# circuit.net
KiCad netlist of a schematic drawn in EAGLE
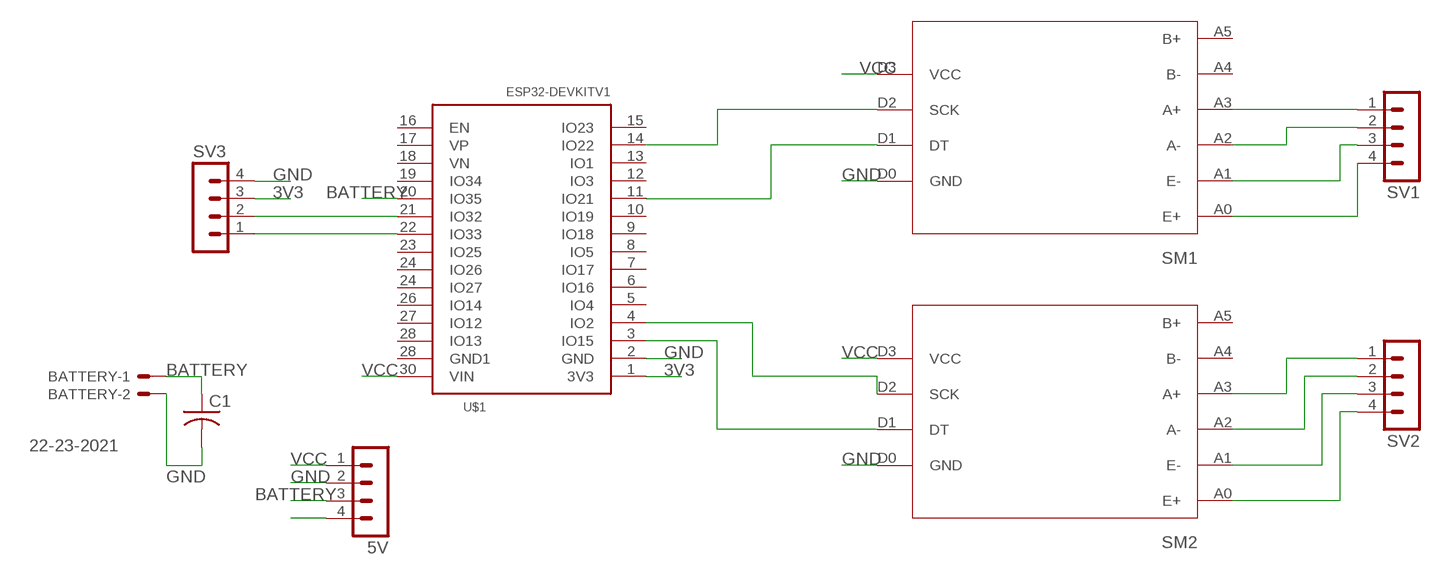
[diagram p0: schematic, sheet 1]

(export (version "E")
  (design (tool "Eeschema 10.0.6"))
  (components
    (comp (ref "5V")
      (value "MA04-1")
      (footprint "eagle-import:MA04-1")
      (libsource (lib "eagle-import") (part "MA04-1"))
    )
    (comp (ref "BATTERY")
      (value "22-23-2021")
      (footprint "eagle-import:22-23-2021")
      (fields (field (name "MF") "MOLEX"))
      (libsource (lib "eagle-import") (part "22-23-2021"))
    )
    (comp (ref "C1")
      (value "C-US050-055X075")
      (footprint "eagle-import:C050-055X075")
      (libsource (lib "eagle-import") (part "C-US050-055X075"))
    )
    (comp (ref "SM1")
      (value "HX711")
      (footprint "eagle-import:HX711")
      (libsource (lib "eagle-import") (part "HX711"))
    )
    (comp (ref "SM2")
      (value "HX711")
      (footprint "eagle-import:HX711")
      (libsource (lib "eagle-import") (part "HX711"))
    )
    (comp (ref "SV1")
      (value "MA04-1")
      (footprint "eagle-import:MA04-1")
      (libsource (lib "eagle-import") (part "MA04-1"))
    )
    (comp (ref "SV2")
      (value "MA04-1")
      (footprint "eagle-import:MA04-1")
      (libsource (lib "eagle-import") (part "MA04-1"))
    )
    (comp (ref "SV3")
      (value "MA04-1")
      (footprint "eagle-import:MA04-1")
      (libsource (lib "eagle-import") (part "MA04-1"))
    )
    (comp (ref "U$1")
      (value "ESP32DEVKITV1")
      (footprint "eagle-import:ESP32-DEVKITV1")
      (libsource (lib "eagle-import") (part "ESP32DEVKITV1"))
    )
  )
  (nets
    (net (code "1") (name "/3V3") (class "Default")
      (node (ref "SV3") (pin "3") (pinfunction "3_3") (pintype "passive"))
      (node (ref "U$1") (pin "1") (pinfunction "3V3_1") (pintype "bidirectional"))
    )
    (net (code "2") (name "/BATTERY") (class "Default")
      (node (ref "5V") (pin "3") (pinfunction "3_3") (pintype "passive"))
      (node (ref "BATTERY") (pin "1") (pinfunction "S_1") (pintype "passive"))
      (node (ref "C1") (pin "1") (pinfunction "1_1") (pintype "passive"))
      (node (ref "U$1") (pin "20") (pinfunction "IO35_20") (pintype "bidirectional"))
    )
    (net (code "3") (name "/GND") (class "Default")
      (node (ref "5V") (pin "2") (pinfunction "2_2") (pintype "passive"))
      (node (ref "BATTERY") (pin "2") (pinfunction "S_2") (pintype "passive"))
      (node (ref "C1") (pin "2") (pinfunction "2_2") (pintype "passive"))
      (node (ref "SM1") (pin "D0") (pinfunction "GND_D0") (pintype "bidirectional"))
      (node (ref "SM2") (pin "D0") (pinfunction "GND_D0") (pintype "bidirectional"))
      (node (ref "SV3") (pin "4") (pinfunction "4_4") (pintype "passive"))
      (node (ref "U$1") (pin "2") (pinfunction "GND_2") (pintype "bidirectional"))
    )
    (net (code "4") (name "/VCC") (class "Default")
      (node (ref "5V") (pin "1") (pinfunction "1_1") (pintype "passive"))
      (node (ref "SM1") (pin "D3") (pinfunction "VCC_D3") (pintype "bidirectional"))
      (node (ref "SM2") (pin "D3") (pinfunction "VCC_D3") (pintype "bidirectional"))
      (node (ref "U$1") (pin "30") (pinfunction "VIN_30") (pintype "bidirectional"))
    )
    (net (code "5") (name "Net-(SM1-A+)") (class "Default")
      (node (ref "SM1") (pin "A3") (pinfunction "A+_A3") (pintype "bidirectional"))
      (node (ref "SV1") (pin "1") (pinfunction "1_1") (pintype "passive"))
    )
    (net (code "6") (name "Net-(SM1-A-)") (class "Default")
      (node (ref "SM1") (pin "A2") (pinfunction "A-_A2") (pintype "bidirectional"))
      (node (ref "SV1") (pin "2") (pinfunction "2_2") (pintype "passive"))
    )
    (net (code "7") (name "Net-(SM1-DT)") (class "Default")
      (node (ref "SM1") (pin "D1") (pinfunction "DT_D1") (pintype "bidirectional"))
      (node (ref "U$1") (pin "11") (pinfunction "IO21_11") (pintype "bidirectional"))
    )
    (net (code "8") (name "Net-(SM1-E+)") (class "Default")
      (node (ref "SM1") (pin "A0") (pinfunction "E+_A0") (pintype "bidirectional"))
      (node (ref "SV1") (pin "4") (pinfunction "4_4") (pintype "passive"))
    )
    (net (code "9") (name "Net-(SM1-E-)") (class "Default")
      (node (ref "SM1") (pin "A1") (pinfunction "E-_A1") (pintype "bidirectional"))
      (node (ref "SV1") (pin "3") (pinfunction "3_3") (pintype "passive"))
    )
    (net (code "10") (name "Net-(SM1-SCK)") (class "Default")
      (node (ref "SM1") (pin "D2") (pinfunction "SCK_D2") (pintype "bidirectional"))
      (node (ref "U$1") (pin "14") (pinfunction "IO22_14") (pintype "bidirectional"))
    )
    (net (code "11") (name "Net-(SM2-A+)") (class "Default")
      (node (ref "SM2") (pin "A3") (pinfunction "A+_A3") (pintype "bidirectional"))
      (node (ref "SV2") (pin "1") (pinfunction "1_1") (pintype "passive"))
    )
    (net (code "12") (name "Net-(SM2-A-)") (class "Default")
      (node (ref "SM2") (pin "A2") (pinfunction "A-_A2") (pintype "bidirectional"))
      (node (ref "SV2") (pin "2") (pinfunction "2_2") (pintype "passive"))
    )
    (net (code "13") (name "Net-(SM2-DT)") (class "Default")
      (node (ref "SM2") (pin "D1") (pinfunction "DT_D1") (pintype "bidirectional"))
      (node (ref "U$1") (pin "3") (pinfunction "IO15_3") (pintype "bidirectional"))
    )
    (net (code "14") (name "Net-(SM2-E+)") (class "Default")
      (node (ref "SM2") (pin "A0") (pinfunction "E+_A0") (pintype "bidirectional"))
      (node (ref "SV2") (pin "4") (pinfunction "4_4") (pintype "passive"))
    )
    (net (code "15") (name "Net-(SM2-E-)") (class "Default")
      (node (ref "SM2") (pin "A1") (pinfunction "E-_A1") (pintype "bidirectional"))
      (node (ref "SV2") (pin "3") (pinfunction "3_3") (pintype "passive"))
    )
    (net (code "16") (name "Net-(SM2-SCK)") (class "Default")
      (node (ref "SM2") (pin "D2") (pinfunction "SCK_D2") (pintype "bidirectional"))
      (node (ref "U$1") (pin "4") (pinfunction "IO2_4") (pintype "bidirectional"))
    )
    (net (code "17") (name "Net-(U$1-IO32)") (class "Default")
      (node (ref "SV3") (pin "2") (pinfunction "2_2") (pintype "passive"))
      (node (ref "U$1") (pin "21") (pinfunction "IO32_21") (pintype "bidirectional"))
    )
    (net (code "18") (name "Net-(U$1-IO33)") (class "Default")
      (node (ref "SV3") (pin "1") (pinfunction "1_1") (pintype "passive"))
      (node (ref "U$1") (pin "22") (pinfunction "IO33_22") (pintype "bidirectional"))
    )
    (net (code "19") (name "unconnected-(5V-Pad4)") (class "Default")
      (node (ref "5V") (pin "4") (pinfunction "4_4") (pintype "passive"))
    )
    (net (code "20") (name "unconnected-(SM1-B+-PadA5)") (class "Default")
      (node (ref "SM1") (pin "A5") (pinfunction "B+_A5") (pintype "bidirectional"))
    )
    (net (code "21") (name "unconnected-(SM1-B--PadA4)") (class "Default")
      (node (ref "SM1") (pin "A4") (pinfunction "B-_A4") (pintype "bidirectional"))
    )
    (net (code "22") (name "unconnected-(SM2-B+-PadA5)") (class "Default")
      (node (ref "SM2") (pin "A5") (pinfunction "B+_A5") (pintype "bidirectional"))
    )
    (net (code "23") (name "unconnected-(SM2-B--PadA4)") (class "Default")
      (node (ref "SM2") (pin "A4") (pinfunction "B-_A4") (pintype "bidirectional"))
    )
    (net (code "24") (name "unconnected-(U$1-EN-Pad16)") (class "Default")
      (node (ref "U$1") (pin "16") (pinfunction "EN_16") (pintype "bidirectional"))
    )
    (net (code "25") (name "unconnected-(U$1-GND1-Pad28)") (class "Default")
      (node (ref "U$1") (pin "28") (pinfunction "GND1_28") (pintype "bidirectional"))
    )
    (net (code "26") (name "unconnected-(U$1-IO1-Pad13)") (class "Default")
      (node (ref "U$1") (pin "13") (pinfunction "IO1_13") (pintype "bidirectional"))
    )
    (net (code "27") (name "unconnected-(U$1-IO3-Pad12)") (class "Default")
      (node (ref "U$1") (pin "12") (pinfunction "IO3_12") (pintype "bidirectional"))
    )
    (net (code "28") (name "unconnected-(U$1-IO4-Pad5)") (class "Default")
      (node (ref "U$1") (pin "5") (pinfunction "IO4_5") (pintype "bidirectional"))
    )
    (net (code "29") (name "unconnected-(U$1-IO5-Pad8)") (class "Default")
      (node (ref "U$1") (pin "8") (pinfunction "IO5_8") (pintype "bidirectional"))
    )
    (net (code "30") (name "unconnected-(U$1-IO12-Pad27)") (class "Default")
      (node (ref "U$1") (pin "27") (pinfunction "IO12_27") (pintype "bidirectional"))
    )
    (net (code "31") (name "unconnected-(U$1-IO13-Pad28)") (class "Default")
      (node (ref "U$1") (pin "28") (pinfunction "IO13_28") (pintype "bidirectional"))
    )
    (net (code "32") (name "unconnected-(U$1-IO14-Pad26)") (class "Default")
      (node (ref "U$1") (pin "26") (pinfunction "IO14_26") (pintype "bidirectional"))
    )
    (net (code "33") (name "unconnected-(U$1-IO16-Pad6)") (class "Default")
      (node (ref "U$1") (pin "6") (pinfunction "IO16_6") (pintype "bidirectional"))
    )
    (net (code "34") (name "unconnected-(U$1-IO17-Pad7)") (class "Default")
      (node (ref "U$1") (pin "7") (pinfunction "IO17_7") (pintype "bidirectional"))
    )
    (net (code "35") (name "unconnected-(U$1-IO18-Pad9)") (class "Default")
      (node (ref "U$1") (pin "9") (pinfunction "IO18_9") (pintype "bidirectional"))
    )
    (net (code "36") (name "unconnected-(U$1-IO19-Pad10)") (class "Default")
      (node (ref "U$1") (pin "10") (pinfunction "IO19_10") (pintype "bidirectional"))
    )
    (net (code "37") (name "unconnected-(U$1-IO23-Pad15)") (class "Default")
      (node (ref "U$1") (pin "15") (pinfunction "IO23_15") (pintype "bidirectional"))
    )
    (net (code "38") (name "unconnected-(U$1-IO25-Pad23)") (class "Default")
      (node (ref "U$1") (pin "23") (pinfunction "IO25_23") (pintype "bidirectional"))
    )
    (net (code "39") (name "unconnected-(U$1-IO26-Pad24)") (class "Default")
      (node (ref "U$1") (pin "24") (pinfunction "IO26_24") (pintype "bidirectional"))
    )
    (net (code "40") (name "unconnected-(U$1-IO27-Pad24)") (class "Default")
      (node (ref "U$1") (pin "24") (pinfunction "IO27_24") (pintype "bidirectional"))
    )
    (net (code "41") (name "unconnected-(U$1-IO34-Pad19)") (class "Default")
      (node (ref "U$1") (pin "19") (pinfunction "IO34_19") (pintype "bidirectional"))
    )
    (net (code "42") (name "unconnected-(U$1-VN-Pad18)") (class "Default")
      (node (ref "U$1") (pin "18") (pinfunction "VN_18") (pintype "bidirectional"))
    )
    (net (code "43") (name "unconnected-(U$1-VP-Pad17)") (class "Default")
      (node (ref "U$1") (pin "17") (pinfunction "VP_17") (pintype "bidirectional"))
    )
  )
)
